# colororgan.net
KiCad netlist of a schematic drawn in EAGLE
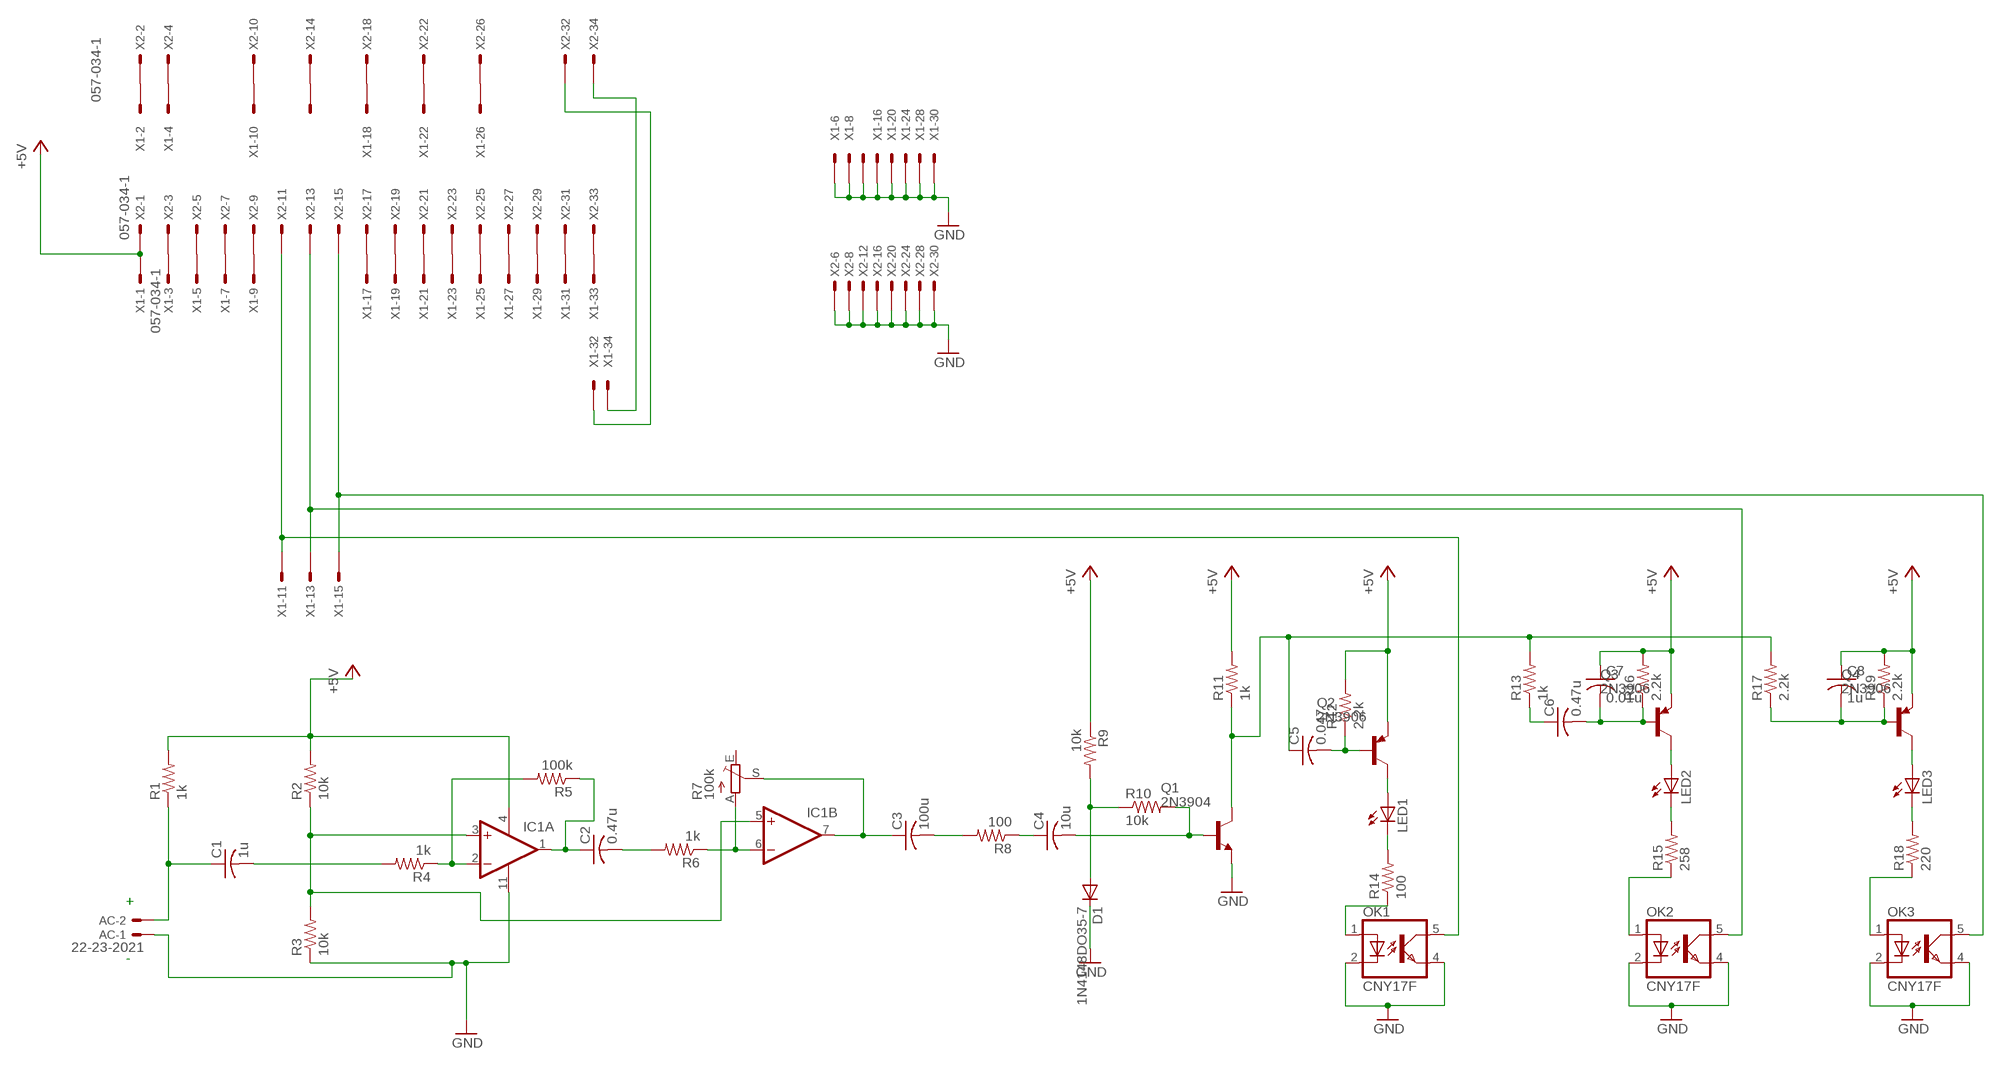
[diagram p0: schematic, sheet 1]

(export (version "E")
  (design (tool "Eeschema 10.0.6"))
  (components
    (comp (ref "AC")
      (value "22-23-2021")
      (footprint "eagle-import:22-23-2021")
      (fields (field (name "MF") "MOLEX"))
      (libsource (lib "eagle-import") (part "22-23-2021"))
    )
    (comp (ref "C1")
      (value "1u")
      (footprint "eagle-import:C025-050X050")
      (libsource (lib "eagle-import") (part "C-US025-050X050"))
    )
    (comp (ref "C2")
      (value "0.47u")
      (footprint "eagle-import:C025-050X050")
      (libsource (lib "eagle-import") (part "C-US025-050X050"))
    )
    (comp (ref "C3")
      (value "100u")
      (footprint "eagle-import:C025-050X050")
      (libsource (lib "eagle-import") (part "C-US025-050X050"))
    )
    (comp (ref "C4")
      (value "10u")
      (footprint "eagle-import:C025-050X050")
      (libsource (lib "eagle-import") (part "C-US025-050X050"))
    )
    (comp (ref "C5")
      (value "0.047")
      (footprint "eagle-import:C025-050X050")
      (libsource (lib "eagle-import") (part "C-US025-050X050"))
    )
    (comp (ref "C6")
      (value "0.47u")
      (footprint "eagle-import:C025-050X050")
      (libsource (lib "eagle-import") (part "C-US025-050X050"))
    )
    (comp (ref "C7")
      (value "0.01u")
      (footprint "eagle-import:C025-050X050")
      (libsource (lib "eagle-import") (part "C-US025-050X050"))
    )
    (comp (ref "C8")
      (value "1u")
      (footprint "eagle-import:C025-050X050")
      (libsource (lib "eagle-import") (part "C-US025-050X050"))
    )
    (comp (ref "D1")
      (value "1N4148DO35-7")
      (footprint "eagle-import:DO35-7")
      (libsource (lib "eagle-import") (part "1N4148DO35-7"))
    )
    (comp (ref "IC1")
      (value "LMV324THR")
      (footprint "eagle-import:DIL14")
      (libsource (lib "eagle-import") (part "LMV324?THR"))
    )
    (comp (ref "LED1")
      (value "LED3MM")
      (footprint "eagle-import:LED3MM")
      (libsource (lib "eagle-import") (part "LED3MM"))
    )
    (comp (ref "LED2")
      (value "LED3MM")
      (footprint "eagle-import:LED3MM")
      (libsource (lib "eagle-import") (part "LED3MM"))
    )
    (comp (ref "LED3")
      (value "LED3MM")
      (footprint "eagle-import:LED3MM")
      (libsource (lib "eagle-import") (part "LED3MM"))
    )
    (comp (ref "OK1")
      (value "CNY17F")
      (footprint "eagle-import:DIL06")
      (fields (field (name "MF") "VISHAY/TELEFUNKEN") (field (name "MPN") "CNY17F-3"))
      (libsource (lib "eagle-import") (part "CNY17F"))
    )
    (comp (ref "OK2")
      (value "CNY17F")
      (footprint "eagle-import:DIL06")
      (fields (field (name "MF") "VISHAY/TELEFUNKEN") (field (name "MPN") "CNY17F-3"))
      (libsource (lib "eagle-import") (part "CNY17F"))
    )
    (comp (ref "OK3")
      (value "CNY17F")
      (footprint "eagle-import:DIL06")
      (fields (field (name "MF") "VISHAY/TELEFUNKEN") (field (name "MPN") "CNY17F-3"))
      (libsource (lib "eagle-import") (part "CNY17F"))
    )
    (comp (ref "Q1")
      (value "2N3904")
      (footprint "eagle-import:TO92")
      (libsource (lib "eagle-import") (part "2N3904"))
    )
    (comp (ref "Q2")
      (value "2N3906")
      (footprint "eagle-import:TO92")
      (libsource (lib "eagle-import") (part "2N3906"))
    )
    (comp (ref "Q3")
      (value "2N3906")
      (footprint "eagle-import:TO92")
      (libsource (lib "eagle-import") (part "2N3906"))
    )
    (comp (ref "Q4")
      (value "2N3906")
      (footprint "eagle-import:TO92")
      (libsource (lib "eagle-import") (part "2N3906"))
    )
    (comp (ref "R1")
      (value "1k")
      (footprint "eagle-import:0207_10")
      (libsource (lib "eagle-import") (part "R-US_0207/10"))
    )
    (comp (ref "R2")
      (value "10k")
      (footprint "eagle-import:0207_10")
      (libsource (lib "eagle-import") (part "R-US_0207/10"))
    )
    (comp (ref "R3")
      (value "10k")
      (footprint "eagle-import:0207_10")
      (libsource (lib "eagle-import") (part "R-US_0207/10"))
    )
    (comp (ref "R4")
      (value "1k")
      (footprint "eagle-import:0207_10")
      (libsource (lib "eagle-import") (part "R-US_0207/10"))
    )
    (comp (ref "R5")
      (value "100k")
      (footprint "eagle-import:0207_10")
      (libsource (lib "eagle-import") (part "R-US_0207/10"))
    )
    (comp (ref "R6")
      (value "1k")
      (footprint "eagle-import:0207_10")
      (libsource (lib "eagle-import") (part "R-US_0207/10"))
    )
    (comp (ref "R7")
      (value "100k")
      (footprint "eagle-import:RS3")
      (libsource (lib "eagle-import") (part "TRIM_EU-RS3"))
    )
    (comp (ref "R8")
      (value "100")
      (footprint "eagle-import:0207_10")
      (libsource (lib "eagle-import") (part "R-US_0207/10"))
    )
    (comp (ref "R9")
      (value "10k")
      (footprint "eagle-import:0207_10")
      (libsource (lib "eagle-import") (part "R-US_0207/10"))
    )
    (comp (ref "R10")
      (value "10k")
      (footprint "eagle-import:0207_10")
      (libsource (lib "eagle-import") (part "R-US_0207/10"))
    )
    (comp (ref "R11")
      (value "1k")
      (footprint "eagle-import:0207_10")
      (libsource (lib "eagle-import") (part "R-US_0207/10"))
    )
    (comp (ref "R12")
      (value "2.2k")
      (footprint "eagle-import:0207_10")
      (libsource (lib "eagle-import") (part "R-US_0207/10"))
    )
    (comp (ref "R13")
      (value "1k")
      (footprint "eagle-import:0207_10")
      (libsource (lib "eagle-import") (part "R-US_0207/10"))
    )
    (comp (ref "R14")
      (value "100")
      (footprint "eagle-import:0207_10")
      (libsource (lib "eagle-import") (part "R-US_0207/10"))
    )
    (comp (ref "R15")
      (value "258")
      (footprint "eagle-import:0207_10")
      (libsource (lib "eagle-import") (part "R-US_0207/10"))
    )
    (comp (ref "R16")
      (value "2.2k")
      (footprint "eagle-import:0207_10")
      (libsource (lib "eagle-import") (part "R-US_0207/10"))
    )
    (comp (ref "R17")
      (value "2.2k")
      (footprint "eagle-import:0207_10")
      (libsource (lib "eagle-import") (part "R-US_0207/10"))
    )
    (comp (ref "R18")
      (value "220")
      (footprint "eagle-import:0207_10")
      (libsource (lib "eagle-import") (part "R-US_0207/10"))
    )
    (comp (ref "R19")
      (value "2.2k")
      (footprint "eagle-import:0207_10")
      (libsource (lib "eagle-import") (part "R-US_0207/10"))
    )
    (comp (ref "X1")
      (value "057-034-1")
      (footprint "eagle-import:057-034-1")
      (libsource (lib "eagle-import") (part "057-034-1"))
    )
    (comp (ref "X2")
      (value "057-034-1")
      (footprint "eagle-import:057-034-1")
      (libsource (lib "eagle-import") (part "057-034-1"))
    )
  )
  (nets
    (net (code "1") (name "+5V") (class "Default")
      (node (ref "C7") (pin "1") (pinfunction "1_1") (pintype "passive"))
      (node (ref "C8") (pin "1") (pinfunction "1_1") (pintype "passive"))
      (node (ref "IC1") (pin "4") (pinfunction "V+_4") (pintype "power_in"))
      (node (ref "Q2") (pin "3") (pinfunction "E_3") (pintype "passive"))
      (node (ref "Q3") (pin "3") (pinfunction "E_3") (pintype "passive"))
      (node (ref "Q4") (pin "3") (pinfunction "E_3") (pintype "passive"))
      (node (ref "R1") (pin "2") (pinfunction "2_2") (pintype "passive"))
      (node (ref "R11") (pin "2") (pinfunction "2_2") (pintype "passive"))
      (node (ref "R12") (pin "2") (pinfunction "2_2") (pintype "passive"))
      (node (ref "R16") (pin "2") (pinfunction "2_2") (pintype "passive"))
      (node (ref "R19") (pin "2") (pinfunction "2_2") (pintype "passive"))
      (node (ref "R2") (pin "2") (pinfunction "2_2") (pintype "passive"))
      (node (ref "R9") (pin "1") (pinfunction "1_1") (pintype "passive"))
      (node (ref "X1") (pin "1") (pinfunction "S_1") (pintype "passive"))
      (node (ref "X2") (pin "1") (pinfunction "S_1") (pintype "passive"))
    )
    (net (code "2") (name "GND") (class "Default")
      (node (ref "AC") (pin "1") (pinfunction "S_1") (pintype "passive"))
      (node (ref "D1") (pin "C") (pinfunction "C_C") (pintype "passive"))
      (node (ref "IC1") (pin "11") (pinfunction "V-_11") (pintype "power_in"))
      (node (ref "OK1") (pin "2") (pinfunction "C_2") (pintype "passive"))
      (node (ref "OK1") (pin "4") (pinfunction "EMIT_4") (pintype "passive"))
      (node (ref "OK2") (pin "2") (pinfunction "C_2") (pintype "passive"))
      (node (ref "OK2") (pin "4") (pinfunction "EMIT_4") (pintype "passive"))
      (node (ref "OK3") (pin "2") (pinfunction "C_2") (pintype "passive"))
      (node (ref "OK3") (pin "4") (pinfunction "EMIT_4") (pintype "passive"))
      (node (ref "Q1") (pin "3") (pinfunction "E_3") (pintype "passive"))
      (node (ref "R3") (pin "1") (pinfunction "1_1") (pintype "passive"))
      (node (ref "X1") (pin "12") (pinfunction "S_12") (pintype "passive"))
      (node (ref "X1") (pin "16") (pinfunction "S_16") (pintype "passive"))
      (node (ref "X1") (pin "20") (pinfunction "S_20") (pintype "passive"))
      (node (ref "X1") (pin "24") (pinfunction "S_24") (pintype "passive"))
      (node (ref "X1") (pin "28") (pinfunction "S_28") (pintype "passive"))
      (node (ref "X1") (pin "30") (pinfunction "S_30") (pintype "passive"))
      (node (ref "X1") (pin "6") (pinfunction "S_6") (pintype "passive"))
      (node (ref "X1") (pin "8") (pinfunction "S_8") (pintype "passive"))
      (node (ref "X2") (pin "12") (pinfunction "S_12") (pintype "passive"))
      (node (ref "X2") (pin "16") (pinfunction "S_16") (pintype "passive"))
      (node (ref "X2") (pin "20") (pinfunction "S_20") (pintype "passive"))
      (node (ref "X2") (pin "24") (pinfunction "S_24") (pintype "passive"))
      (node (ref "X2") (pin "28") (pinfunction "S_28") (pintype "passive"))
      (node (ref "X2") (pin "30") (pinfunction "S_30") (pintype "passive"))
      (node (ref "X2") (pin "6") (pinfunction "S_6") (pintype "passive"))
      (node (ref "X2") (pin "8") (pinfunction "S_8") (pintype "passive"))
    )
    (net (code "3") (name "Net-(ACB-S)") (class "Default")
      (node (ref "AC") (pin "2") (pinfunction "S_2") (pintype "passive"))
      (node (ref "C1") (pin "1") (pinfunction "1_1") (pintype "passive"))
      (node (ref "R1") (pin "1") (pinfunction "1_1") (pintype "passive"))
    )
    (net (code "4") (name "Net-(C1-Pad2)") (class "Default")
      (node (ref "C1") (pin "2") (pinfunction "2_2") (pintype "passive"))
      (node (ref "R4") (pin "2") (pinfunction "2_2") (pintype "passive"))
    )
    (net (code "5") (name "Net-(C2-Pad2)") (class "Default")
      (node (ref "C2") (pin "2") (pinfunction "2_2") (pintype "passive"))
      (node (ref "R6") (pin "2") (pinfunction "2_2") (pintype "passive"))
    )
    (net (code "6") (name "Net-(C3-Pad2)") (class "Default")
      (node (ref "C3") (pin "2") (pinfunction "2_2") (pintype "passive"))
      (node (ref "R8") (pin "2") (pinfunction "2_2") (pintype "passive"))
    )
    (net (code "7") (name "Net-(C4-Pad1)") (class "Default")
      (node (ref "C4") (pin "1") (pinfunction "1_1") (pintype "passive"))
      (node (ref "R8") (pin "1") (pinfunction "1_1") (pintype "passive"))
    )
    (net (code "8") (name "Net-(C6-Pad1)") (class "Default")
      (node (ref "C6") (pin "1") (pinfunction "1_1") (pintype "passive"))
      (node (ref "R13") (pin "1") (pinfunction "1_1") (pintype "passive"))
    )
    (net (code "9") (name "Net-(D1-PadA)") (class "Default")
      (node (ref "D1") (pin "A") (pinfunction "A_A") (pintype "passive"))
      (node (ref "R10") (pin "1") (pinfunction "1_1") (pintype "passive"))
      (node (ref "R9") (pin "2") (pinfunction "2_2") (pintype "passive"))
    )
    (net (code "10") (name "Net-(IC1A-+IN)") (class "Default")
      (node (ref "IC1") (pin "3") (pinfunction "+IN_3") (pintype "input"))
      (node (ref "IC1") (pin "5") (pinfunction "+IN_5") (pintype "input"))
      (node (ref "R2") (pin "1") (pinfunction "1_1") (pintype "passive"))
      (node (ref "R3") (pin "2") (pinfunction "2_2") (pintype "passive"))
    )
    (net (code "11") (name "Net-(IC1A--IN)") (class "Default")
      (node (ref "IC1") (pin "2") (pinfunction "-IN_2") (pintype "input"))
      (node (ref "R4") (pin "1") (pinfunction "1_1") (pintype "passive"))
      (node (ref "R5") (pin "2") (pinfunction "2_2") (pintype "passive"))
    )
    (net (code "12") (name "Net-(IC1A-OUT)") (class "Default")
      (node (ref "C2") (pin "1") (pinfunction "1_1") (pintype "passive"))
      (node (ref "IC1") (pin "1") (pinfunction "OUT_1") (pintype "output"))
      (node (ref "R5") (pin "1") (pinfunction "1_1") (pintype "passive"))
    )
    (net (code "13") (name "Net-(IC1B--IN)") (class "Default")
      (node (ref "IC1") (pin "6") (pinfunction "-IN_6") (pintype "input"))
      (node (ref "R6") (pin "1") (pinfunction "1_1") (pintype "passive"))
      (node (ref "R7") (pin "A") (pinfunction "A_A") (pintype "passive"))
    )
    (net (code "14") (name "Net-(IC1B-OUT)") (class "Default")
      (node (ref "C3") (pin "1") (pinfunction "1_1") (pintype "passive"))
      (node (ref "IC1") (pin "7") (pinfunction "OUT_7") (pintype "output"))
      (node (ref "R7") (pin "S") (pinfunction "S_S") (pintype "passive"))
    )
    (net (code "15") (name "Net-(LED1-C)") (class "Default")
      (node (ref "LED1") (pin "K") (pinfunction "C_K") (pintype "passive"))
      (node (ref "R14") (pin "2") (pinfunction "2_2") (pintype "passive"))
    )
    (net (code "16") (name "Net-(LED2-C)") (class "Default")
      (node (ref "LED2") (pin "K") (pinfunction "C_K") (pintype "passive"))
      (node (ref "R15") (pin "2") (pinfunction "2_2") (pintype "passive"))
    )
    (net (code "17") (name "Net-(LED3-C)") (class "Default")
      (node (ref "LED3") (pin "K") (pinfunction "C_K") (pintype "passive"))
      (node (ref "R18") (pin "2") (pinfunction "2_2") (pintype "passive"))
    )
    (net (code "18") (name "Net-(OK1-A)") (class "Default")
      (node (ref "OK1") (pin "1") (pinfunction "A_1") (pintype "passive"))
      (node (ref "R14") (pin "1") (pinfunction "1_1") (pintype "passive"))
    )
    (net (code "19") (name "Net-(OK1-COL)") (class "Default")
      (node (ref "OK1") (pin "5") (pinfunction "COL_5") (pintype "passive"))
      (node (ref "X1") (pin "11") (pinfunction "S_11") (pintype "passive"))
      (node (ref "X2") (pin "11") (pinfunction "S_11") (pintype "passive"))
    )
    (net (code "20") (name "Net-(OK2-A)") (class "Default")
      (node (ref "OK2") (pin "1") (pinfunction "A_1") (pintype "passive"))
      (node (ref "R15") (pin "1") (pinfunction "1_1") (pintype "passive"))
    )
    (net (code "21") (name "Net-(OK2-COL)") (class "Default")
      (node (ref "OK2") (pin "5") (pinfunction "COL_5") (pintype "passive"))
      (node (ref "X1") (pin "13") (pinfunction "S_13") (pintype "passive"))
      (node (ref "X2") (pin "13") (pinfunction "S_13") (pintype "passive"))
    )
    (net (code "22") (name "Net-(OK3-A)") (class "Default")
      (node (ref "OK3") (pin "1") (pinfunction "A_1") (pintype "passive"))
      (node (ref "R18") (pin "1") (pinfunction "1_1") (pintype "passive"))
    )
    (net (code "23") (name "Net-(OK3-COL)") (class "Default")
      (node (ref "OK3") (pin "5") (pinfunction "COL_5") (pintype "passive"))
      (node (ref "X1") (pin "15") (pinfunction "S_15") (pintype "passive"))
      (node (ref "X2") (pin "15") (pinfunction "S_15") (pintype "passive"))
    )
    (net (code "24") (name "Net-(Q1-B)") (class "Default")
      (node (ref "C4") (pin "2") (pinfunction "2_2") (pintype "passive"))
      (node (ref "Q1") (pin "2") (pinfunction "B_2") (pintype "passive"))
      (node (ref "R10") (pin "2") (pinfunction "2_2") (pintype "passive"))
    )
    (net (code "25") (name "Net-(Q1-C)") (class "Default")
      (node (ref "C5") (pin "1") (pinfunction "1_1") (pintype "passive"))
      (node (ref "Q1") (pin "1") (pinfunction "C_1") (pintype "passive"))
      (node (ref "R11") (pin "1") (pinfunction "1_1") (pintype "passive"))
      (node (ref "R13") (pin "2") (pinfunction "2_2") (pintype "passive"))
      (node (ref "R17") (pin "2") (pinfunction "2_2") (pintype "passive"))
    )
    (net (code "26") (name "Net-(Q2-B)") (class "Default")
      (node (ref "C5") (pin "2") (pinfunction "2_2") (pintype "passive"))
      (node (ref "Q2") (pin "2") (pinfunction "B_2") (pintype "passive"))
      (node (ref "R12") (pin "1") (pinfunction "1_1") (pintype "passive"))
    )
    (net (code "27") (name "Net-(Q2-C)") (class "Default")
      (node (ref "LED1") (pin "A") (pinfunction "A_A") (pintype "passive"))
      (node (ref "Q2") (pin "1") (pinfunction "C_1") (pintype "passive"))
    )
    (net (code "28") (name "Net-(Q3-B)") (class "Default")
      (node (ref "C6") (pin "2") (pinfunction "2_2") (pintype "passive"))
      (node (ref "C7") (pin "2") (pinfunction "2_2") (pintype "passive"))
      (node (ref "Q3") (pin "2") (pinfunction "B_2") (pintype "passive"))
      (node (ref "R16") (pin "1") (pinfunction "1_1") (pintype "passive"))
    )
    (net (code "29") (name "Net-(Q3-C)") (class "Default")
      (node (ref "LED2") (pin "A") (pinfunction "A_A") (pintype "passive"))
      (node (ref "Q3") (pin "1") (pinfunction "C_1") (pintype "passive"))
    )
    (net (code "30") (name "Net-(Q4-B)") (class "Default")
      (node (ref "C8") (pin "2") (pinfunction "2_2") (pintype "passive"))
      (node (ref "Q4") (pin "2") (pinfunction "B_2") (pintype "passive"))
      (node (ref "R17") (pin "1") (pinfunction "1_1") (pintype "passive"))
      (node (ref "R19") (pin "1") (pinfunction "1_1") (pintype "passive"))
    )
    (net (code "31") (name "Net-(Q4-C)") (class "Default")
      (node (ref "LED3") (pin "A") (pinfunction "A_A") (pintype "passive"))
      (node (ref "Q4") (pin "1") (pinfunction "C_1") (pintype "passive"))
    )
    (net (code "32") (name "Net-(X1AA-S)") (class "Default")
      (node (ref "X1") (pin "33") (pinfunction "S_33") (pintype "passive"))
      (node (ref "X2") (pin "33") (pinfunction "S_33") (pintype "passive"))
    )
    (net (code "33") (name "Net-(X1AB-S)") (class "Default")
      (node (ref "X1") (pin "34") (pinfunction "S_34") (pintype "passive"))
      (node (ref "X2") (pin "34") (pinfunction "S_34") (pintype "passive"))
    )
    (net (code "34") (name "Net-(X1AC-S)") (class "Default")
      (node (ref "X1") (pin "4") (pinfunction "S_4") (pintype "passive"))
      (node (ref "X2") (pin "4") (pinfunction "S_4") (pintype "passive"))
    )
    (net (code "35") (name "Net-(X1AD-S)") (class "Default")
      (node (ref "X1") (pin "5") (pinfunction "S_5") (pintype "passive"))
      (node (ref "X2") (pin "5") (pinfunction "S_5") (pintype "passive"))
    )
    (net (code "36") (name "Net-(X1AF-S)") (class "Default")
      (node (ref "X1") (pin "7") (pinfunction "S_7") (pintype "passive"))
      (node (ref "X2") (pin "7") (pinfunction "S_7") (pintype "passive"))
    )
    (net (code "37") (name "Net-(X1AH-S)") (class "Default")
      (node (ref "X1") (pin "9") (pinfunction "S_9") (pintype "passive"))
      (node (ref "X2") (pin "9") (pinfunction "S_9") (pintype "passive"))
    )
    (net (code "38") (name "Net-(X1B-S)") (class "Default")
      (node (ref "X1") (pin "10") (pinfunction "S_10") (pintype "passive"))
      (node (ref "X2") (pin "10") (pinfunction "S_10") (pintype "passive"))
    )
    (net (code "39") (name "Net-(X1F-S)") (class "Default")
      (node (ref "X1") (pin "14") (pinfunction "S_14") (pintype "passive"))
      (node (ref "X2") (pin "14") (pinfunction "S_14") (pintype "passive"))
    )
    (net (code "40") (name "Net-(X1I-S)") (class "Default")
      (node (ref "X1") (pin "17") (pinfunction "S_17") (pintype "passive"))
      (node (ref "X2") (pin "17") (pinfunction "S_17") (pintype "passive"))
    )
    (net (code "41") (name "Net-(X1J-S)") (class "Default")
      (node (ref "X1") (pin "18") (pinfunction "S_18") (pintype "passive"))
      (node (ref "X2") (pin "18") (pinfunction "S_18") (pintype "passive"))
    )
    (net (code "42") (name "Net-(X1K-S)") (class "Default")
      (node (ref "X1") (pin "19") (pinfunction "S_19") (pintype "passive"))
      (node (ref "X2") (pin "19") (pinfunction "S_19") (pintype "passive"))
    )
    (net (code "43") (name "Net-(X1L-S)") (class "Default")
      (node (ref "X1") (pin "2") (pinfunction "S_2") (pintype "passive"))
      (node (ref "X2") (pin "2") (pinfunction "S_2") (pintype "passive"))
    )
    (net (code "44") (name "Net-(X1N-S)") (class "Default")
      (node (ref "X1") (pin "21") (pinfunction "S_21") (pintype "passive"))
      (node (ref "X2") (pin "21") (pinfunction "S_21") (pintype "passive"))
    )
    (net (code "45") (name "Net-(X1O-S)") (class "Default")
      (node (ref "X1") (pin "22") (pinfunction "S_22") (pintype "passive"))
      (node (ref "X2") (pin "22") (pinfunction "S_22") (pintype "passive"))
    )
    (net (code "46") (name "Net-(X1P-S)") (class "Default")
      (node (ref "X1") (pin "23") (pinfunction "S_23") (pintype "passive"))
      (node (ref "X2") (pin "23") (pinfunction "S_23") (pintype "passive"))
    )
    (net (code "47") (name "Net-(X1R-S)") (class "Default")
      (node (ref "X1") (pin "25") (pinfunction "S_25") (pintype "passive"))
      (node (ref "X2") (pin "25") (pinfunction "S_25") (pintype "passive"))
    )
    (net (code "48") (name "Net-(X1S-S)") (class "Default")
      (node (ref "X1") (pin "26") (pinfunction "S_26") (pintype "passive"))
      (node (ref "X2") (pin "26") (pinfunction "S_26") (pintype "passive"))
    )
    (net (code "49") (name "Net-(X1T-S)") (class "Default")
      (node (ref "X1") (pin "27") (pinfunction "S_27") (pintype "passive"))
      (node (ref "X2") (pin "27") (pinfunction "S_27") (pintype "passive"))
    )
    (net (code "50") (name "Net-(X1V-S)") (class "Default")
      (node (ref "X1") (pin "29") (pinfunction "S_29") (pintype "passive"))
      (node (ref "X2") (pin "29") (pinfunction "S_29") (pintype "passive"))
    )
    (net (code "51") (name "Net-(X1W-S)") (class "Default")
      (node (ref "X1") (pin "3") (pinfunction "S_3") (pintype "passive"))
      (node (ref "X2") (pin "3") (pinfunction "S_3") (pintype "passive"))
    )
    (net (code "52") (name "Net-(X1Y-S)") (class "Default")
      (node (ref "X1") (pin "31") (pinfunction "S_31") (pintype "passive"))
      (node (ref "X2") (pin "31") (pinfunction "S_31") (pintype "passive"))
    )
    (net (code "53") (name "Net-(X1Z-S)") (class "Default")
      (node (ref "X1") (pin "32") (pinfunction "S_32") (pintype "passive"))
      (node (ref "X2") (pin "32") (pinfunction "S_32") (pintype "passive"))
    )
    (net (code "54") (name "unconnected-(R7-PadE)") (class "Default")
      (node (ref "R7") (pin "E") (pinfunction "E_E") (pintype "passive"))
    )
  )
)
